# 12_-CAMERA_POWER.net
KiCad netlist of a schematic drawn in Altium Designer
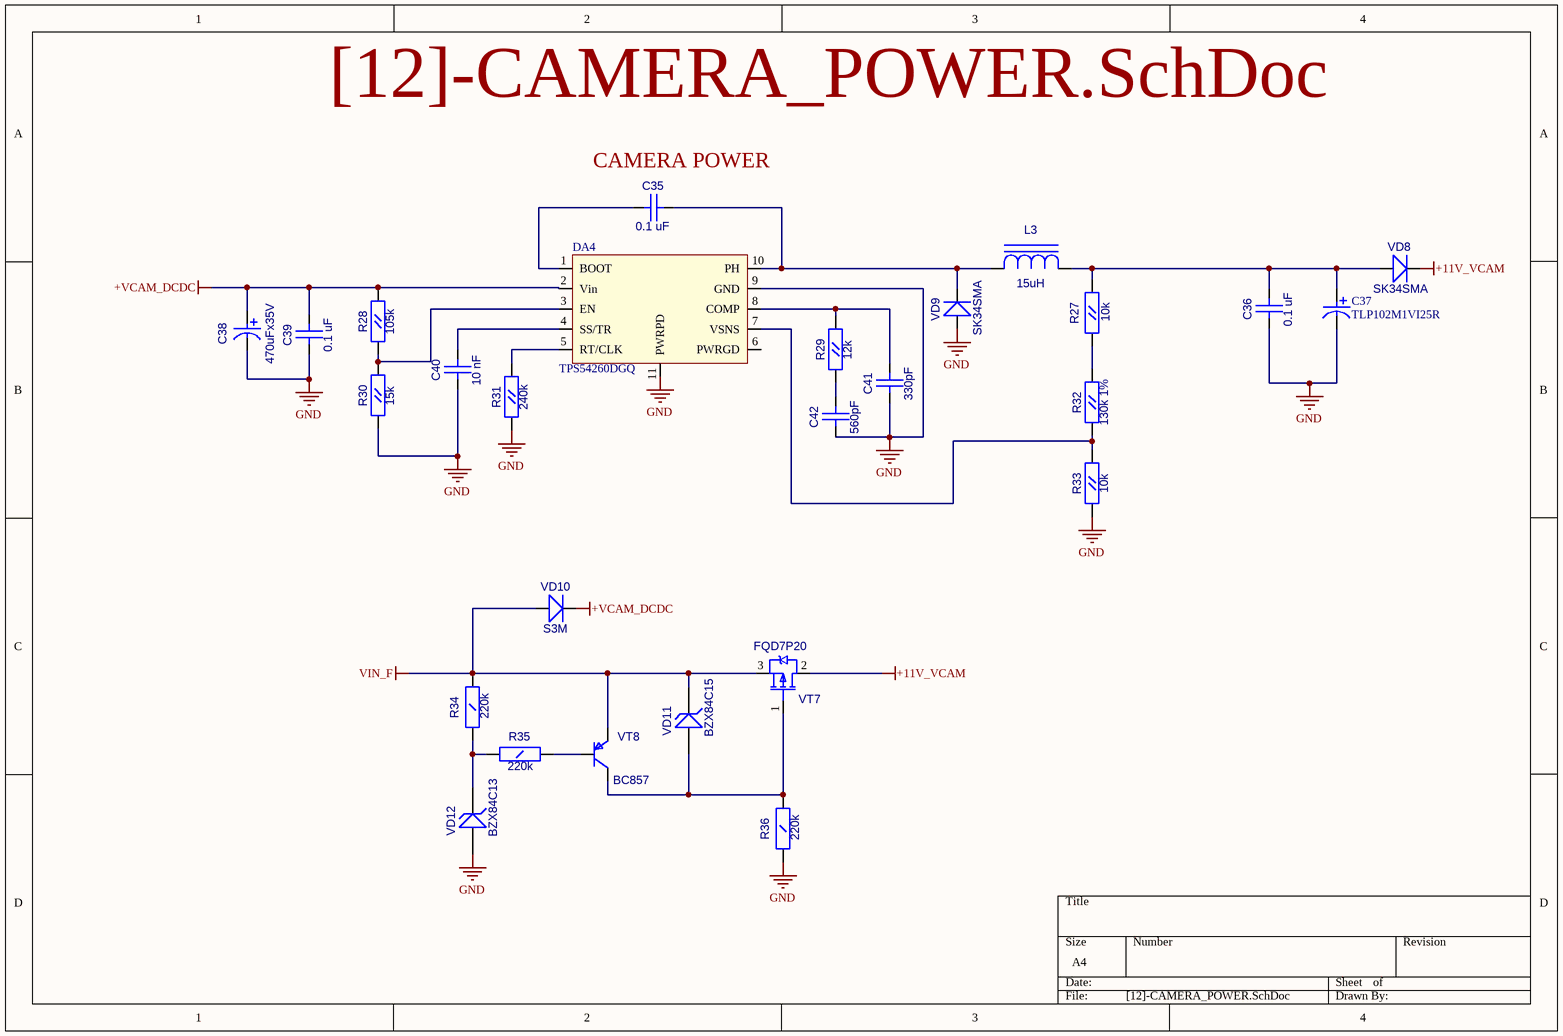
[diagram p0: [12]-CAMERA_POWER.SchDoc]

(export (version "E")
  (design (tool "Eeschema 10.0.6"))
  (components
    (comp (ref "C35")
      (value "0.1 uF")
      (footprint "CC0603")
      (description "CC0603")
      (libsource (lib "gprs_modem_2") (part "CC0603"))
    )
    (comp (ref "C36")
      (value "0.1 uF")
      (footprint "CC0603")
      (description "CC0603")
      (libsource (lib "gprs_modem_2") (part "CC0603"))
    )
    (comp (ref "C37")
      (value "TLP102M1VI25R")
      (footprint "CAP_13x26")
      (libsource (lib "fizik_lib (1)") (part "SUPERCAP_10F"))
    )
    (comp (ref "C38")
      (value "470uFx35V")
      (footprint "CC16X10_CAP0.5(1)(Primary)")
      (description "CAP0.5(1)")
      (libsource (lib "gprs_modem_2") (part "CAP0.5(1)"))
    )
    (comp (ref "C39")
      (value "0.1 uF")
      (footprint "CC0603")
      (description "CC0603")
      (libsource (lib "gprs_modem_2") (part "CC0603"))
    )
    (comp (ref "C40")
      (value "10 nF")
      (footprint "CC0603")
      (description "CC0603")
      (libsource (lib "gprs_modem_2") (part "CC0603"))
    )
    (comp (ref "C41")
      (value "330pF")
      (footprint "CC0603")
      (description "CC0603")
      (libsource (lib "gprs_modem_2") (part "CC0603"))
    )
    (comp (ref "C42")
      (value "560pF")
      (footprint "CC0603")
      (description "CC0603")
      (libsource (lib "gprs_modem_2") (part "CC0603"))
    )
    (comp (ref "DA4")
      (value "TPS54260DGQ")
      (footprint "S-PDSO-G10")
      (libsource (lib "gprs_modem_2") (part "TPS54260DGQ"))
    )
    (comp (ref "L3")
      (value "15uH")
      (footprint "SDR0805")
      (description "SDR0805")
      (libsource (lib "gprs_modem_2") (part "SDR0805"))
    )
    (comp (ref "R27")
      (value "10k")
      (footprint "RC0603")
      (description "RC0603")
      (libsource (lib "fizik_lib") (part "RC0603"))
    )
    (comp (ref "R28")
      (value "105k")
      (footprint "RC0603")
      (description "RC0603")
      (libsource (lib "gprs_modem_2") (part "RC0603"))
    )
    (comp (ref "R29")
      (value "12k")
      (footprint "RC0603")
      (description "RC0603")
      (libsource (lib "gprs_modem_2") (part "RC0603"))
    )
    (comp (ref "R30")
      (value "15k")
      (footprint "RC0603")
      (description "RC0603")
      (libsource (lib "gprs_modem_2") (part "RC0603"))
    )
    (comp (ref "R31")
      (value "240k")
      (footprint "RC0603")
      (description "RC0603")
      (libsource (lib "gprs_modem_2") (part "RC0603"))
    )
    (comp (ref "R32")
      (value "130k 1%")
      (footprint "RC0603")
      (description "RC0603")
      (libsource (lib "gprs_modem_2") (part "RC0603"))
    )
    (comp (ref "R33")
      (value "10k")
      (footprint "RC0603")
      (description "RC0603")
      (libsource (lib "gprs_modem_2") (part "RC0603"))
    )
    (comp (ref "R34")
      (value "220k")
      (footprint "RC1206")
      (description "RC1206")
      (libsource (lib "fizik_lib") (part "RC1206"))
    )
    (comp (ref "R35")
      (value "220k")
      (footprint "RC1206")
      (description "RC1206")
      (libsource (lib "fizik_lib") (part "RC1206"))
    )
    (comp (ref "R36")
      (value "220k")
      (footprint "RC1206")
      (description "RC1206")
      (libsource (lib "fizik_lib") (part "RC1206"))
    )
    (comp (ref "VD8")
      (value "SK34SMA")
      (footprint "SMA")
      (description "Schottky Rectifier")
      (libsource (lib "gprs_modem") (part "SK34SMA"))
    )
    (comp (ref "VD9")
      (value "SK34SMA")
      (footprint "SMA")
      (description "Schottky Rectifier")
      (libsource (lib "gprs_modem") (part "SK34SMA"))
    )
    (comp (ref "VD10")
      (value "S3M")
      (footprint "SMC")
      (description "Schottky Rectifier")
      (libsource (lib "fizik_lib") (part "S3A"))
    )
    (comp (ref "VD11")
      (value "BZX84C15")
      (footprint "SOT-23(123)")
      (description "Zener Voltage Regulator Diode")
      (libsource (lib "fizik_lib") (part "BZX84"))
    )
    (comp (ref "VD12")
      (value "BZX84C13")
      (footprint "SOT-23(123)")
      (description "Zener Voltage Regulator Diode")
      (libsource (lib "fizik_lib") (part "BZX84"))
    )
    (comp (ref "VT7")
      (value "FQD7P20")
      (footprint "D-PAK(TO-252AA)")
      (description "HEXFET Power MOSFET")
      (libsource (lib "gprs_modem_2") (part "IRFR9220"))
    )
    (comp (ref "VT8")
      (value "BC857")
      (footprint "SOT-23(123)")
      (description "PNP 100ma transistor")
      (libsource (lib "gprs_modem_2") (part "BC857B"))
    )
  )
  (nets
    (net (code "1") (name "+11V_VCAM") (class "Default")
      (node (ref "VD8") (pin "2") (pinfunction "K_2") (pintype "passive"))
      (node (ref "VT7") (pin "2") (pinfunction "D_2") (pintype "passive"))
    )
    (net (code "2") (name "+VCAM_DCDC") (class "Default")
      (node (ref "C38") (pin "2") (pintype "passive"))
      (node (ref "C39") (pin "1") (pinfunction "A_1") (pintype "passive"))
      (node (ref "DA4") (pin "2") (pinfunction "Vin_2") (pintype "passive"))
      (node (ref "R28") (pin "2") (pinfunction "B_2") (pintype "passive"))
      (node (ref "VD10") (pin "2") (pinfunction "K_2") (pintype "passive"))
    )
    (net (code "3") (name "GND") (class "Default")
      (node (ref "C36") (pin "2") (pinfunction "B_2") (pintype "passive"))
      (node (ref "C37") (pin "1") (pintype "passive"))
      (node (ref "C38") (pin "1") (pintype "passive"))
      (node (ref "C39") (pin "2") (pinfunction "B_2") (pintype "passive"))
      (node (ref "C40") (pin "2") (pinfunction "B_2") (pintype "passive"))
      (node (ref "C41") (pin "2") (pinfunction "B_2") (pintype "passive"))
      (node (ref "C42") (pin "2") (pinfunction "B_2") (pintype "passive"))
      (node (ref "DA4") (pin "11") (pinfunction "PWRPD_11") (pintype "passive"))
      (node (ref "DA4") (pin "9") (pinfunction "GND_9") (pintype "passive"))
      (node (ref "R30") (pin "1") (pinfunction "A_1") (pintype "passive"))
      (node (ref "R31") (pin "1") (pinfunction "A_1") (pintype "passive"))
      (node (ref "R33") (pin "1") (pinfunction "A_1") (pintype "passive"))
      (node (ref "R36") (pin "1") (pinfunction "A_1") (pintype "passive"))
      (node (ref "VD12") (pin "1") (pinfunction "A_1") (pintype "passive"))
      (node (ref "VD9") (pin "1") (pinfunction "A_1") (pintype "passive"))
    )
    (net (code "4") (name "Net-(C35-A)") (class "Default")
      (node (ref "C35") (pin "1") (pinfunction "A_1") (pintype "passive"))
      (node (ref "DA4") (pin "10") (pinfunction "PH_10") (pintype "passive"))
      (node (ref "L3") (pin "1") (pinfunction "C_1") (pintype "passive"))
      (node (ref "VD9") (pin "2") (pinfunction "K_2") (pintype "passive"))
    )
    (net (code "5") (name "Net-(C35-B)") (class "Default")
      (node (ref "C35") (pin "2") (pinfunction "B_2") (pintype "passive"))
      (node (ref "DA4") (pin "1") (pinfunction "BOOT_1") (pintype "passive"))
    )
    (net (code "6") (name "Net-(C36-A)") (class "Default")
      (node (ref "C36") (pin "1") (pinfunction "A_1") (pintype "passive"))
      (node (ref "C37") (pin "2") (pintype "passive"))
      (node (ref "L3") (pin "2") (pinfunction "A_2") (pintype "passive"))
      (node (ref "R27") (pin "2") (pinfunction "B_2") (pintype "passive"))
      (node (ref "VD8") (pin "1") (pinfunction "A_1") (pintype "passive"))
    )
    (net (code "7") (name "Net-(C40-A)") (class "Default")
      (node (ref "C40") (pin "1") (pinfunction "A_1") (pintype "passive"))
      (node (ref "DA4") (pin "4") (pinfunction "SS/TR_4") (pintype "passive"))
    )
    (net (code "8") (name "Net-(C41-A)") (class "Default")
      (node (ref "C41") (pin "1") (pinfunction "A_1") (pintype "passive"))
      (node (ref "DA4") (pin "8") (pinfunction "COMP_8") (pintype "passive"))
      (node (ref "R29") (pin "2") (pinfunction "B_2") (pintype "passive"))
    )
    (net (code "9") (name "Net-(C42-A)") (class "Default")
      (node (ref "C42") (pin "1") (pinfunction "A_1") (pintype "passive"))
      (node (ref "R29") (pin "1") (pinfunction "A_1") (pintype "passive"))
    )
    (net (code "10") (name "Net-(DA4-EN)") (class "Default")
      (node (ref "DA4") (pin "3") (pinfunction "EN_3") (pintype "passive"))
      (node (ref "R28") (pin "1") (pinfunction "A_1") (pintype "passive"))
      (node (ref "R30") (pin "2") (pinfunction "B_2") (pintype "passive"))
    )
    (net (code "11") (name "Net-(DA4-RT{slash}CLK)") (class "Default")
      (node (ref "DA4") (pin "5") (pinfunction "RT/CLK_5") (pintype "passive"))
      (node (ref "R31") (pin "2") (pinfunction "B_2") (pintype "passive"))
    )
    (net (code "12") (name "Net-(DA4-VSNS)") (class "Default")
      (node (ref "DA4") (pin "7") (pinfunction "VSNS_7") (pintype "passive"))
      (node (ref "R32") (pin "1") (pinfunction "A_1") (pintype "passive"))
      (node (ref "R33") (pin "2") (pinfunction "B_2") (pintype "passive"))
    )
    (net (code "13") (name "Net-(R27-A)") (class "Default")
      (node (ref "R27") (pin "1") (pinfunction "A_1") (pintype "passive"))
      (node (ref "R32") (pin "2") (pinfunction "B_2") (pintype "passive"))
    )
    (net (code "14") (name "Net-(R34-A)") (class "Default")
      (node (ref "R34") (pin "1") (pinfunction "A_1") (pintype "passive"))
      (node (ref "R35") (pin "1") (pinfunction "A_1") (pintype "passive"))
      (node (ref "VD12") (pin "3") (pinfunction "K_3") (pintype "passive"))
    )
    (net (code "15") (name "Net-(R35-B)") (class "Default")
      (node (ref "R35") (pin "2") (pinfunction "B_2") (pintype "passive"))
      (node (ref "VT8") (pin "1") (pinfunction "B_1") (pintype "passive"))
    )
    (net (code "16") (name "Net-(R36-B)") (class "Default")
      (node (ref "R36") (pin "2") (pinfunction "B_2") (pintype "passive"))
      (node (ref "VD11") (pin "1") (pinfunction "A_1") (pintype "passive"))
      (node (ref "VT7") (pin "1") (pinfunction "G_1") (pintype "passive"))
      (node (ref "VT8") (pin "3") (pinfunction "C_3") (pintype "passive"))
    )
    (net (code "17") (name "VIN_F") (class "Default")
      (node (ref "R34") (pin "2") (pinfunction "B_2") (pintype "passive"))
      (node (ref "VD10") (pin "1") (pinfunction "A_1") (pintype "passive"))
      (node (ref "VD11") (pin "3") (pinfunction "K_3") (pintype "passive"))
      (node (ref "VT7") (pin "3") (pinfunction "S_3") (pintype "passive"))
      (node (ref "VT8") (pin "2") (pinfunction "E_2") (pintype "passive"))
    )
    (net (code "18") (name "unconnected-(DA4-PWRGD-Pad6)") (class "Default")
      (node (ref "DA4") (pin "6") (pinfunction "PWRGD_6") (pintype "passive"))
    )
  )
)
